# SPI2Parallel_v1p1.net
KiCad netlist of a schematic drawn in EAGLE
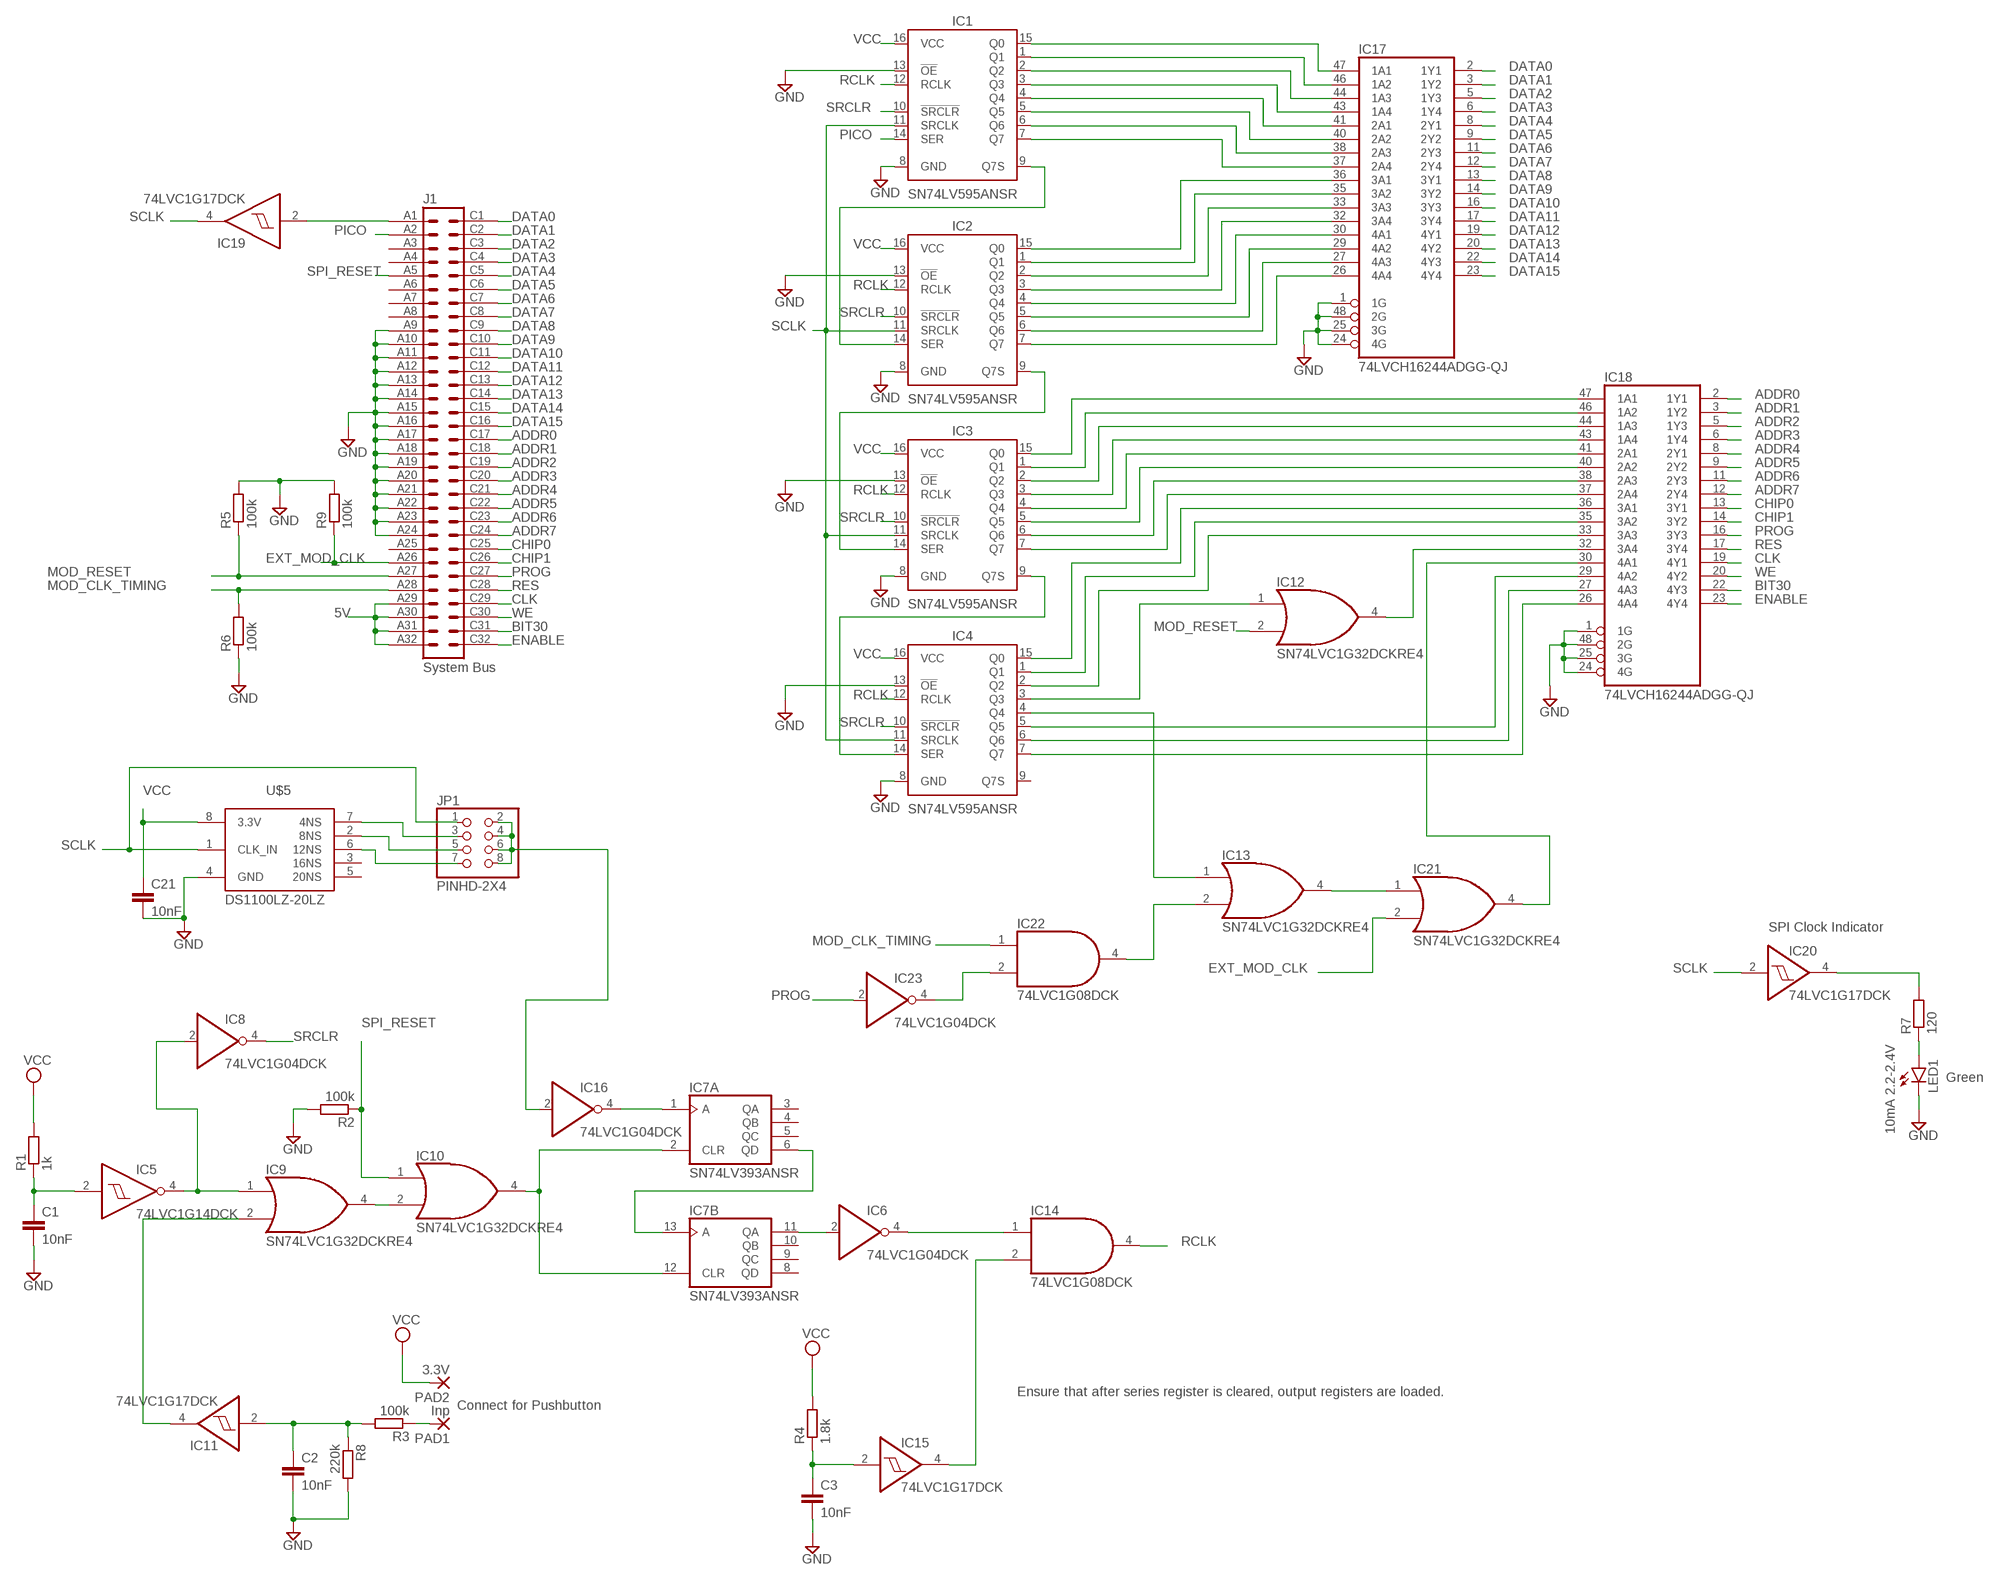
[diagram p0: schematic, sheet 1]
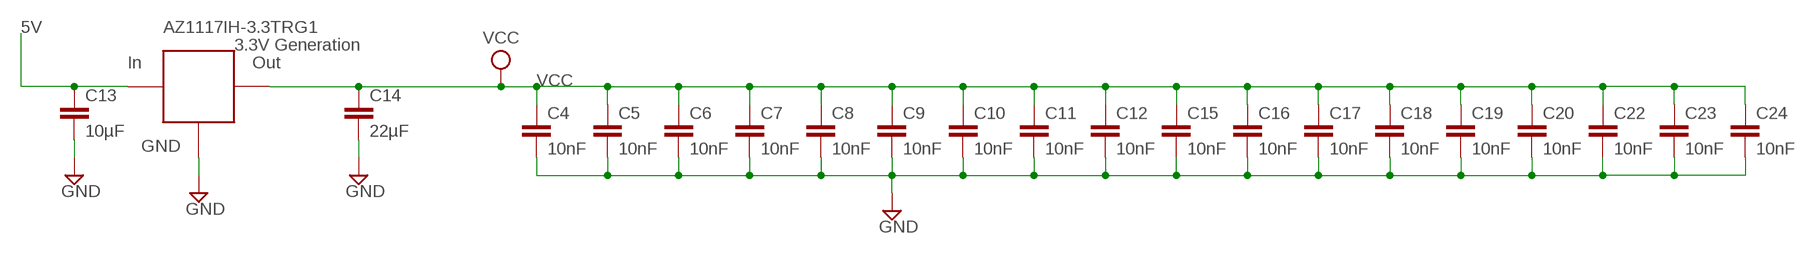
[diagram p1: schematic, sheet 2]

(export (version "E")
  (design (tool "Eeschema 10.0.6"))
  (components
    (comp (ref "C1")
      (value "10nF")
      (footprint "eagle-import:C0603")
      (libsource (lib "eagle-import") (part "C-EUC0603"))
    )
    (comp (ref "C2")
      (value "10nF")
      (footprint "eagle-import:C0603")
      (libsource (lib "eagle-import") (part "C-EUC0603"))
    )
    (comp (ref "C3")
      (value "10nF")
      (footprint "eagle-import:C0603")
      (libsource (lib "eagle-import") (part "C-EUC0603"))
    )
    (comp (ref "C21")
      (value "10nF")
      (footprint "eagle-import:C0603")
      (libsource (lib "eagle-import") (part "C-EUC0603"))
    )
    (comp (ref "IC1")
      (value "SN74LV595ANSR")
      (footprint "eagle-import:SOIC127P600X175-16N")
      (fields (field (name "MANUFACTURER") "Generic"))
      (libsource (lib "eagle-import") (part "74HC595_SOIC"))
    )
    (comp (ref "IC2")
      (value "SN74LV595ANSR")
      (footprint "eagle-import:SOIC127P600X175-16N")
      (fields (field (name "MANUFACTURER") "Generic"))
      (libsource (lib "eagle-import") (part "74HC595_SOIC"))
    )
    (comp (ref "IC3")
      (value "SN74LV595ANSR")
      (footprint "eagle-import:SOIC127P600X175-16N")
      (fields (field (name "MANUFACTURER") "Generic"))
      (libsource (lib "eagle-import") (part "74HC595_SOIC"))
    )
    (comp (ref "IC4")
      (value "SN74LV595ANSR")
      (footprint "eagle-import:SOIC127P600X175-16N")
      (fields (field (name "MANUFACTURER") "Generic"))
      (libsource (lib "eagle-import") (part "74HC595_SOIC"))
    )
    (comp (ref "IC5")
      (value "74LVC1G14DCK")
      (footprint "eagle-import:SC70-5")
      (libsource (lib "eagle-import") (part "741G14DCKLVC"))
    )
    (comp (ref "IC6")
      (value "74LVC1G04DCK")
      (footprint "eagle-import:SC70-5")
      (libsource (lib "eagle-import") (part "741G04DCKLVC"))
    )
    (comp (ref "IC7")
      (value "SN74LV393ANSR")
      (footprint "eagle-import:SO14")
      (libsource (lib "eagle-import") (part "74393DAC"))
    )
    (comp (ref "IC8")
      (value "74LVC1G04DCK")
      (footprint "eagle-import:SC70-5")
      (libsource (lib "eagle-import") (part "741G04DCKLVC"))
    )
    (comp (ref "IC9")
      (value "SN74LVC1G32DCKRE4")
      (footprint "eagle-import:SC70-5")
      (libsource (lib "eagle-import") (part "741G32DCKAHCT"))
    )
    (comp (ref "IC10")
      (value "SN74LVC1G32DCKRE4")
      (footprint "eagle-import:SC70-5")
      (libsource (lib "eagle-import") (part "741G32DCKAHCT"))
    )
    (comp (ref "IC11")
      (value "74LVC1G17DCK")
      (footprint "eagle-import:SC70-5")
      (libsource (lib "eagle-import") (part "741G17DCKLVC"))
    )
    (comp (ref "IC12")
      (value "SN74LVC1G32DCKRE4")
      (footprint "eagle-import:SC70-5")
      (libsource (lib "eagle-import") (part "741G32DCKAUC"))
    )
    (comp (ref "IC13")
      (value "SN74LVC1G32DCKRE4")
      (footprint "eagle-import:SC70-5")
      (libsource (lib "eagle-import") (part "741G32DCKAUC"))
    )
    (comp (ref "IC14")
      (value "74LVC1G08DCK")
      (footprint "eagle-import:SC70-5")
      (libsource (lib "eagle-import") (part "741G08DCKLVC"))
    )
    (comp (ref "IC15")
      (value "74LVC1G17DCK")
      (footprint "eagle-import:SC70-5")
      (libsource (lib "eagle-import") (part "741G17DCKLVC"))
    )
    (comp (ref "IC16")
      (value "74LVC1G04DCK")
      (footprint "eagle-import:SC70-5")
      (libsource (lib "eagle-import") (part "741G04DCKLVC"))
    )
    (comp (ref "IC17")
      (value "74LVCH16244ADGG-QJ")
      (footprint "eagle-import:SSOP48DL")
      (libsource (lib "eagle-import") (part "74AC16244"))
    )
    (comp (ref "IC18")
      (value "74LVCH16244ADGG-QJ")
      (footprint "eagle-import:SSOP48DL")
      (libsource (lib "eagle-import") (part "74AC16244"))
    )
    (comp (ref "IC19")
      (value "74LVC1G17DCK")
      (footprint "eagle-import:SC70-5")
      (libsource (lib "eagle-import") (part "74xx-little-us_87_741G17DCKLVC"))
    )
    (comp (ref "IC20")
      (value "74LVC1G17DCK")
      (footprint "eagle-import:SC70-5")
      (libsource (lib "eagle-import") (part "741G17DCKLVC"))
    )
    (comp (ref "IC21")
      (value "SN74LVC1G32DCKRE4")
      (footprint "eagle-import:SC70-5")
      (libsource (lib "eagle-import") (part "741G32DCKAUC"))
    )
    (comp (ref "IC22")
      (value "74LVC1G08DCK")
      (footprint "eagle-import:SC70-5")
      (libsource (lib "eagle-import") (part "741G08DCKLVC"))
    )
    (comp (ref "IC23")
      (value "74LVC1G04DCK")
      (footprint "eagle-import:SC70-5")
      (libsource (lib "eagle-import") (part "741G04DCKLVC"))
    )
    (comp (ref "J1")
      (value "System Bus")
      (footprint "eagle-import:VG64P")
      (libsource (lib "eagle-import") (part "VG64P"))
    )
    (comp (ref "JP1")
      (value "PINHD-2X4")
      (footprint "eagle-import:2X04")
      (libsource (lib "eagle-import") (part "PINHD-2X4"))
    )
    (comp (ref "LED1")
      (value "10mA 2.2-2.4V")
      (footprint "eagle-import:LED3MM")
      (libsource (lib "eagle-import") (part "LED3MM"))
    )
    (comp (ref "PAD1")
      (value "Inp")
      (footprint "eagle-import:SMD2,54-5,08")
      (libsource (lib "eagle-import") (part "SMD5"))
    )
    (comp (ref "PAD2")
      (value "3.3V")
      (footprint "eagle-import:SMD2,54-5,08")
      (libsource (lib "eagle-import") (part "SMD5"))
    )
    (comp (ref "R1")
      (value "1k")
      (footprint "eagle-import:R0603")
      (libsource (lib "eagle-import") (part "R-EU_R0603"))
    )
    (comp (ref "R2")
      (value "100k")
      (footprint "eagle-import:R0603")
      (libsource (lib "eagle-import") (part "R-EU_R0603"))
    )
    (comp (ref "R3")
      (value "100k")
      (footprint "eagle-import:R0603")
      (libsource (lib "eagle-import") (part "R-EU_R0603"))
    )
    (comp (ref "R4")
      (value "1.8k")
      (footprint "eagle-import:R0603")
      (libsource (lib "eagle-import") (part "R-EU_R0603"))
    )
    (comp (ref "R5")
      (value "100k")
      (footprint "eagle-import:R0603")
      (libsource (lib "eagle-import") (part "R-EU_R0603"))
    )
    (comp (ref "R6")
      (value "100k")
      (footprint "eagle-import:R0603")
      (libsource (lib "eagle-import") (part "R-EU_R0603"))
    )
    (comp (ref "R7")
      (value "120")
      (footprint "eagle-import:R0603")
      (libsource (lib "eagle-import") (part "R-EU_R0603"))
    )
    (comp (ref "R8")
      (value "220k")
      (footprint "eagle-import:R0603")
      (libsource (lib "eagle-import") (part "R-EU_R0603"))
    )
    (comp (ref "R9")
      (value "100k")
      (footprint "eagle-import:R0603")
      (libsource (lib "eagle-import") (part "R-EU_R0603"))
    )
    (comp (ref "U$5")
      (value "DS1100LZ-20LZ")
      (footprint "eagle-import:SO-08")
      (libsource (lib "eagle-import") (part "DS1100LZ-20LZ"))
    )
    (comp (ref "C4")
      (value "10nF")
      (footprint "eagle-import:C0603")
      (libsource (lib "eagle-import") (part "C-EUC0603"))
    )
    (comp (ref "C5")
      (value "10nF")
      (footprint "eagle-import:C0603")
      (libsource (lib "eagle-import") (part "C-EUC0603"))
    )
    (comp (ref "C6")
      (value "10nF")
      (footprint "eagle-import:C0603")
      (libsource (lib "eagle-import") (part "C-EUC0603"))
    )
    (comp (ref "C7")
      (value "10nF")
      (footprint "eagle-import:C0603")
      (libsource (lib "eagle-import") (part "C-EUC0603"))
    )
    (comp (ref "C8")
      (value "10nF")
      (footprint "eagle-import:C0603")
      (libsource (lib "eagle-import") (part "C-EUC0603"))
    )
    (comp (ref "C9")
      (value "10nF")
      (footprint "eagle-import:C0603")
      (libsource (lib "eagle-import") (part "C-EUC0603"))
    )
    (comp (ref "C10")
      (value "10nF")
      (footprint "eagle-import:C0603")
      (libsource (lib "eagle-import") (part "C-EUC0603"))
    )
    (comp (ref "C11")
      (value "10nF")
      (footprint "eagle-import:C0603")
      (libsource (lib "eagle-import") (part "C-EUC0603"))
    )
    (comp (ref "C12")
      (value "10nF")
      (footprint "eagle-import:C0603")
      (libsource (lib "eagle-import") (part "C-EUC0603"))
    )
    (comp (ref "C13")
      (value "10µF")
      (footprint "eagle-import:C1206")
      (libsource (lib "eagle-import") (part "C-EUC1206"))
    )
    (comp (ref "C14")
      (value "22µF")
      (footprint "eagle-import:C1206")
      (libsource (lib "eagle-import") (part "C-EUC1206"))
    )
    (comp (ref "C15")
      (value "10nF")
      (footprint "eagle-import:C0603")
      (libsource (lib "eagle-import") (part "C-EUC0603"))
    )
    (comp (ref "C16")
      (value "10nF")
      (footprint "eagle-import:C0603")
      (libsource (lib "eagle-import") (part "C-EUC0603"))
    )
    (comp (ref "C17")
      (value "10nF")
      (footprint "eagle-import:C0603")
      (libsource (lib "eagle-import") (part "C-EUC0603"))
    )
    (comp (ref "C18")
      (value "10nF")
      (footprint "eagle-import:C0603")
      (libsource (lib "eagle-import") (part "C-EUC0603"))
    )
    (comp (ref "C19")
      (value "10nF")
      (footprint "eagle-import:C0603")
      (libsource (lib "eagle-import") (part "C-EUC0603"))
    )
    (comp (ref "C20")
      (value "10nF")
      (footprint "eagle-import:C0603")
      (libsource (lib "eagle-import") (part "C-EUC0603"))
    )
    (comp (ref "C22")
      (value "10nF")
      (footprint "eagle-import:C0603")
      (libsource (lib "eagle-import") (part "C-EUC0603"))
    )
    (comp (ref "C23")
      (value "10nF")
      (footprint "eagle-import:C0603")
      (libsource (lib "eagle-import") (part "C-EUC0603"))
    )
    (comp (ref "C24")
      (value "10nF")
      (footprint "eagle-import:C0603")
      (libsource (lib "eagle-import") (part "C-EUC0603"))
    )
    (comp (ref "U$9")
      (value "AZ1117IH-3.3TRG1")
      (footprint "eagle-import:SOT223")
      (libsource (lib "eagle-import") (part "LT1117"))
    )
  )
  (nets
    (net (code "1") (name "5V") (class "Default")
      (node (ref "C13") (pin "1") (pinfunction "1_1") (pintype "passive"))
      (node (ref "J1") (pin "A29") (pinfunction "A29_A29") (pintype "passive"))
      (node (ref "J1") (pin "A30") (pinfunction "A30_A30") (pintype "passive"))
      (node (ref "J1") (pin "A31") (pinfunction "A31_A31") (pintype "passive"))
      (node (ref "J1") (pin "A32") (pinfunction "A32_A32") (pintype "passive"))
      (node (ref "U$9") (pin "3") (pinfunction "IN_3") (pintype "bidirectional"))
    )
    (net (code "2") (name "ADDR0") (class "Default")
      (node (ref "IC18") (pin "2") (pinfunction "1Y1_2") (pintype "tri_state"))
      (node (ref "J1") (pin "C17") (pinfunction "C17_C17") (pintype "passive"))
    )
    (net (code "3") (name "ADDR1") (class "Default")
      (node (ref "IC18") (pin "3") (pinfunction "1Y2_3") (pintype "tri_state"))
      (node (ref "J1") (pin "C18") (pinfunction "C18_C18") (pintype "passive"))
    )
    (net (code "4") (name "ADDR2") (class "Default")
      (node (ref "IC18") (pin "5") (pinfunction "1Y3_5") (pintype "tri_state"))
      (node (ref "J1") (pin "C19") (pinfunction "C19_C19") (pintype "passive"))
    )
    (net (code "5") (name "ADDR3") (class "Default")
      (node (ref "IC18") (pin "6") (pinfunction "1Y4_6") (pintype "tri_state"))
      (node (ref "J1") (pin "C20") (pinfunction "C20_C20") (pintype "passive"))
    )
    (net (code "6") (name "ADDR4") (class "Default")
      (node (ref "IC18") (pin "8") (pinfunction "2Y1_8") (pintype "tri_state"))
      (node (ref "J1") (pin "C21") (pinfunction "C21_C21") (pintype "passive"))
    )
    (net (code "7") (name "ADDR5") (class "Default")
      (node (ref "IC18") (pin "9") (pinfunction "2Y2_9") (pintype "tri_state"))
      (node (ref "J1") (pin "C22") (pinfunction "C22_C22") (pintype "passive"))
    )
    (net (code "8") (name "ADDR6") (class "Default")
      (node (ref "IC18") (pin "11") (pinfunction "2Y3_11") (pintype "tri_state"))
      (node (ref "J1") (pin "C23") (pinfunction "C23_C23") (pintype "passive"))
    )
    (net (code "9") (name "ADDR7") (class "Default")
      (node (ref "IC18") (pin "12") (pinfunction "2Y4_12") (pintype "tri_state"))
      (node (ref "J1") (pin "C24") (pinfunction "C24_C24") (pintype "passive"))
    )
    (net (code "10") (name "BIT30") (class "Default")
      (node (ref "IC18") (pin "22") (pinfunction "4Y3_22") (pintype "tri_state"))
      (node (ref "J1") (pin "C31") (pinfunction "C31_C31") (pintype "passive"))
    )
    (net (code "11") (name "CHIP0") (class "Default")
      (node (ref "IC18") (pin "13") (pinfunction "3Y1_13") (pintype "tri_state"))
      (node (ref "J1") (pin "C25") (pinfunction "C25_C25") (pintype "passive"))
    )
    (net (code "12") (name "CHIP1") (class "Default")
      (node (ref "IC18") (pin "14") (pinfunction "3Y2_14") (pintype "tri_state"))
      (node (ref "J1") (pin "C26") (pinfunction "C26_C26") (pintype "passive"))
    )
    (net (code "13") (name "CLK") (class "Default")
      (node (ref "IC18") (pin "19") (pinfunction "4Y1_19") (pintype "tri_state"))
      (node (ref "J1") (pin "C29") (pinfunction "C29_C29") (pintype "passive"))
    )
    (net (code "14") (name "DATA0") (class "Default")
      (node (ref "IC17") (pin "2") (pinfunction "1Y1_2") (pintype "tri_state"))
      (node (ref "J1") (pin "C1") (pinfunction "C1_C1") (pintype "passive"))
    )
    (net (code "15") (name "DATA1") (class "Default")
      (node (ref "IC17") (pin "3") (pinfunction "1Y2_3") (pintype "tri_state"))
      (node (ref "J1") (pin "C2") (pinfunction "C2_C2") (pintype "passive"))
    )
    (net (code "16") (name "DATA2") (class "Default")
      (node (ref "IC17") (pin "5") (pinfunction "1Y3_5") (pintype "tri_state"))
      (node (ref "J1") (pin "C3") (pinfunction "C3_C3") (pintype "passive"))
    )
    (net (code "17") (name "DATA3") (class "Default")
      (node (ref "IC17") (pin "6") (pinfunction "1Y4_6") (pintype "tri_state"))
      (node (ref "J1") (pin "C4") (pinfunction "C4_C4") (pintype "passive"))
    )
    (net (code "18") (name "DATA4") (class "Default")
      (node (ref "IC17") (pin "8") (pinfunction "2Y1_8") (pintype "tri_state"))
      (node (ref "J1") (pin "C5") (pinfunction "C5_C5") (pintype "passive"))
    )
    (net (code "19") (name "DATA5") (class "Default")
      (node (ref "IC17") (pin "9") (pinfunction "2Y2_9") (pintype "tri_state"))
      (node (ref "J1") (pin "C6") (pinfunction "C6_C6") (pintype "passive"))
    )
    (net (code "20") (name "DATA6") (class "Default")
      (node (ref "IC17") (pin "11") (pinfunction "2Y3_11") (pintype "tri_state"))
      (node (ref "J1") (pin "C7") (pinfunction "C7_C7") (pintype "passive"))
    )
    (net (code "21") (name "DATA7") (class "Default")
      (node (ref "IC17") (pin "12") (pinfunction "2Y4_12") (pintype "tri_state"))
      (node (ref "J1") (pin "C8") (pinfunction "C8_C8") (pintype "passive"))
    )
    (net (code "22") (name "DATA8") (class "Default")
      (node (ref "IC17") (pin "13") (pinfunction "3Y1_13") (pintype "tri_state"))
      (node (ref "J1") (pin "C9") (pinfunction "C9_C9") (pintype "passive"))
    )
    (net (code "23") (name "DATA9") (class "Default")
      (node (ref "IC17") (pin "14") (pinfunction "3Y2_14") (pintype "tri_state"))
      (node (ref "J1") (pin "C10") (pinfunction "C10_C10") (pintype "passive"))
    )
    (net (code "24") (name "DATA10") (class "Default")
      (node (ref "IC17") (pin "16") (pinfunction "3Y3_16") (pintype "tri_state"))
      (node (ref "J1") (pin "C11") (pinfunction "C11_C11") (pintype "passive"))
    )
    (net (code "25") (name "DATA11") (class "Default")
      (node (ref "IC17") (pin "17") (pinfunction "3Y4_17") (pintype "tri_state"))
      (node (ref "J1") (pin "C12") (pinfunction "C12_C12") (pintype "passive"))
    )
    (net (code "26") (name "DATA12") (class "Default")
      (node (ref "IC17") (pin "19") (pinfunction "4Y1_19") (pintype "tri_state"))
      (node (ref "J1") (pin "C13") (pinfunction "C13_C13") (pintype "passive"))
    )
    (net (code "27") (name "DATA13") (class "Default")
      (node (ref "IC17") (pin "20") (pinfunction "4Y2_20") (pintype "tri_state"))
      (node (ref "J1") (pin "C14") (pinfunction "C14_C14") (pintype "passive"))
    )
    (net (code "28") (name "DATA14") (class "Default")
      (node (ref "IC17") (pin "22") (pinfunction "4Y3_22") (pintype "tri_state"))
      (node (ref "J1") (pin "C15") (pinfunction "C15_C15") (pintype "passive"))
    )
    (net (code "29") (name "DATA15") (class "Default")
      (node (ref "IC17") (pin "23") (pinfunction "4Y4_23") (pintype "tri_state"))
      (node (ref "J1") (pin "C16") (pinfunction "C16_C16") (pintype "passive"))
    )
    (net (code "30") (name "ENABLE") (class "Default")
      (node (ref "IC18") (pin "23") (pinfunction "4Y4_23") (pintype "tri_state"))
      (node (ref "J1") (pin "C32") (pinfunction "C32_C32") (pintype "passive"))
    )
    (net (code "31") (name "EXT_MOD_CLK") (class "Default")
      (node (ref "IC21") (pin "2") (pinfunction "I1_2") (pintype "input"))
      (node (ref "J1") (pin "A26") (pinfunction "A26_A26") (pintype "passive"))
      (node (ref "R9") (pin "1") (pinfunction "1_1") (pintype "passive"))
    )
    (net (code "32") (name "GND") (class "Default")
      (node (ref "C1") (pin "2") (pinfunction "2_2") (pintype "passive"))
      (node (ref "C10") (pin "2") (pinfunction "2_2") (pintype "passive"))
      (node (ref "C11") (pin "2") (pinfunction "2_2") (pintype "passive"))
      (node (ref "C12") (pin "2") (pinfunction "2_2") (pintype "passive"))
      (node (ref "C13") (pin "2") (pinfunction "2_2") (pintype "passive"))
      (node (ref "C14") (pin "2") (pinfunction "2_2") (pintype "passive"))
      (node (ref "C15") (pin "2") (pinfunction "2_2") (pintype "passive"))
      (node (ref "C16") (pin "2") (pinfunction "2_2") (pintype "passive"))
      (node (ref "C17") (pin "2") (pinfunction "2_2") (pintype "passive"))
      (node (ref "C18") (pin "2") (pinfunction "2_2") (pintype "passive"))
      (node (ref "C19") (pin "2") (pinfunction "2_2") (pintype "passive"))
      (node (ref "C2") (pin "2") (pinfunction "2_2") (pintype "passive"))
      (node (ref "C20") (pin "2") (pinfunction "2_2") (pintype "passive"))
      (node (ref "C21") (pin "2") (pinfunction "2_2") (pintype "passive"))
      (node (ref "C22") (pin "2") (pinfunction "2_2") (pintype "passive"))
      (node (ref "C23") (pin "2") (pinfunction "2_2") (pintype "passive"))
      (node (ref "C24") (pin "2") (pinfunction "2_2") (pintype "passive"))
      (node (ref "C3") (pin "2") (pinfunction "2_2") (pintype "passive"))
      (node (ref "C4") (pin "2") (pinfunction "2_2") (pintype "passive"))
      (node (ref "C5") (pin "2") (pinfunction "2_2") (pintype "passive"))
      (node (ref "C6") (pin "2") (pinfunction "2_2") (pintype "passive"))
      (node (ref "C7") (pin "2") (pinfunction "2_2") (pintype "passive"))
      (node (ref "C8") (pin "2") (pinfunction "2_2") (pintype "passive"))
      (node (ref "C9") (pin "2") (pinfunction "2_2") (pintype "passive"))
      (node (ref "IC1") (pin "13") (pinfunction "~{OE}_13") (pintype "output"))
      (node (ref "IC1") (pin "8") (pinfunction "GND_8") (pintype "bidirectional"))
      (node (ref "IC17") (pin "1") (pinfunction "1G_1") (pintype "input"))
      (node (ref "IC17") (pin "24") (pinfunction "4G_24") (pintype "input"))
      (node (ref "IC17") (pin "25") (pinfunction "3G_25") (pintype "input"))
      (node (ref "IC17") (pin "48") (pinfunction "2G_48") (pintype "input"))
      (node (ref "IC18") (pin "1") (pinfunction "1G_1") (pintype "input"))
      (node (ref "IC18") (pin "24") (pinfunction "4G_24") (pintype "input"))
      (node (ref "IC18") (pin "25") (pinfunction "3G_25") (pintype "input"))
      (node (ref "IC18") (pin "48") (pinfunction "2G_48") (pintype "input"))
      (node (ref "IC2") (pin "13") (pinfunction "~{OE}_13") (pintype "output"))
      (node (ref "IC2") (pin "8") (pinfunction "GND_8") (pintype "bidirectional"))
      (node (ref "IC3") (pin "13") (pinfunction "~{OE}_13") (pintype "output"))
      (node (ref "IC3") (pin "8") (pinfunction "GND_8") (pintype "bidirectional"))
      (node (ref "IC4") (pin "13") (pinfunction "~{OE}_13") (pintype "output"))
      (node (ref "IC4") (pin "8") (pinfunction "GND_8") (pintype "bidirectional"))
      (node (ref "J1") (pin "A10") (pinfunction "A10_A10") (pintype "passive"))
      (node (ref "J1") (pin "A11") (pinfunction "A11_A11") (pintype "passive"))
      (node (ref "J1") (pin "A12") (pinfunction "A12_A12") (pintype "passive"))
      (node (ref "J1") (pin "A13") (pinfunction "A13_A13") (pintype "passive"))
      (node (ref "J1") (pin "A14") (pinfunction "A14_A14") (pintype "passive"))
      (node (ref "J1") (pin "A15") (pinfunction "A15_A15") (pintype "passive"))
      (node (ref "J1") (pin "A16") (pinfunction "A16_A16") (pintype "passive"))
      (node (ref "J1") (pin "A17") (pinfunction "A17_A17") (pintype "passive"))
      (node (ref "J1") (pin "A18") (pinfunction "A18_A18") (pintype "passive"))
      (node (ref "J1") (pin "A19") (pinfunction "A19_A19") (pintype "passive"))
      (node (ref "J1") (pin "A20") (pinfunction "A20_A20") (pintype "passive"))
      (node (ref "J1") (pin "A21") (pinfunction "A21_A21") (pintype "passive"))
      (node (ref "J1") (pin "A22") (pinfunction "A22_A22") (pintype "passive"))
      (node (ref "J1") (pin "A23") (pinfunction "A23_A23") (pintype "passive"))
      (node (ref "J1") (pin "A24") (pinfunction "A24_A24") (pintype "passive"))
      (node (ref "J1") (pin "A9") (pinfunction "A9_A9") (pintype "passive"))
      (node (ref "LED1") (pin "K") (pinfunction "C_K") (pintype "passive"))
      (node (ref "R2") (pin "2") (pinfunction "2_2") (pintype "passive"))
      (node (ref "R5") (pin "2") (pinfunction "2_2") (pintype "passive"))
      (node (ref "R6") (pin "1") (pinfunction "1_1") (pintype "passive"))
      (node (ref "R8") (pin "2") (pinfunction "2_2") (pintype "passive"))
      (node (ref "R9") (pin "2") (pinfunction "2_2") (pintype "passive"))
      (node (ref "U$5") (pin "4") (pinfunction "GND_4") (pintype "bidirectional"))
      (node (ref "U$9") (pin "1") (pinfunction "GND_1") (pintype "bidirectional"))
    )
    (net (code "33") (name "MOD_CLK_TIMING") (class "Default")
      (node (ref "IC22") (pin "1") (pinfunction "I0_1") (pintype "input"))
      (node (ref "J1") (pin "A28") (pinfunction "A28_A28") (pintype "passive"))
      (node (ref "R6") (pin "2") (pinfunction "2_2") (pintype "passive"))
    )
    (net (code "34") (name "MOD_RESET") (class "Default")
      (node (ref "IC12") (pin "2") (pinfunction "I1_2") (pintype "input"))
      (node (ref "J1") (pin "A27") (pinfunction "A27_A27") (pintype "passive"))
      (node (ref "R5") (pin "1") (pinfunction "1_1") (pintype "passive"))
    )
    (net (code "35") (name "Net-(IC1-Q0)") (class "Default")
      (node (ref "IC1") (pin "15") (pinfunction "Q0_15") (pintype "output"))
      (node (ref "IC17") (pin "47") (pinfunction "1A1_47") (pintype "input"))
    )
    (net (code "36") (name "Net-(IC1-Q1)") (class "Default")
      (node (ref "IC1") (pin "1") (pinfunction "Q1_1") (pintype "output"))
      (node (ref "IC17") (pin "46") (pinfunction "1A2_46") (pintype "input"))
    )
    (net (code "37") (name "Net-(IC1-Q2)") (class "Default")
      (node (ref "IC1") (pin "2") (pinfunction "Q2_2") (pintype "output"))
      (node (ref "IC17") (pin "44") (pinfunction "1A3_44") (pintype "input"))
    )
    (net (code "38") (name "Net-(IC1-Q3)") (class "Default")
      (node (ref "IC1") (pin "3") (pinfunction "Q3_3") (pintype "output"))
      (node (ref "IC17") (pin "43") (pinfunction "1A4_43") (pintype "input"))
    )
    (net (code "39") (name "Net-(IC1-Q4)") (class "Default")
      (node (ref "IC1") (pin "4") (pinfunction "Q4_4") (pintype "output"))
      (node (ref "IC17") (pin "41") (pinfunction "2A1_41") (pintype "input"))
    )
    (net (code "40") (name "Net-(IC1-Q5)") (class "Default")
      (node (ref "IC1") (pin "5") (pinfunction "Q5_5") (pintype "output"))
      (node (ref "IC17") (pin "40") (pinfunction "2A2_40") (pintype "input"))
    )
    (net (code "41") (name "Net-(IC1-Q6)") (class "Default")
      (node (ref "IC1") (pin "6") (pinfunction "Q6_6") (pintype "output"))
      (node (ref "IC17") (pin "38") (pinfunction "2A3_38") (pintype "input"))
    )
    (net (code "42") (name "Net-(IC1-Q7)") (class "Default")
      (node (ref "IC1") (pin "7") (pinfunction "Q7_7") (pintype "output"))
      (node (ref "IC17") (pin "37") (pinfunction "2A4_37") (pintype "input"))
    )
    (net (code "43") (name "Net-(IC1-Q7S)") (class "Default")
      (node (ref "IC1") (pin "9") (pinfunction "Q7S_9") (pintype "output"))
      (node (ref "IC2") (pin "14") (pinfunction "SER_14") (pintype "input"))
    )
    (net (code "44") (name "Net-(IC2-Q7S)") (class "Default")
      (node (ref "IC2") (pin "9") (pinfunction "Q7S_9") (pintype "output"))
      (node (ref "IC3") (pin "14") (pinfunction "SER_14") (pintype "input"))
    )
    (net (code "45") (name "Net-(IC3-Q7S)") (class "Default")
      (node (ref "IC3") (pin "9") (pinfunction "Q7S_9") (pintype "output"))
      (node (ref "IC4") (pin "14") (pinfunction "SER_14") (pintype "input"))
    )
    (net (code "46") (name "Net-(IC5A-I)") (class "Default")
      (node (ref "C1") (pin "1") (pinfunction "1_1") (pintype "passive"))
      (node (ref "IC5") (pin "2") (pinfunction "I_2") (pintype "input"))
      (node (ref "R1") (pin "1") (pinfunction "1_1") (pintype "passive"))
    )
    (net (code "47") (name "Net-(IC5A-O)") (class "Default")
      (node (ref "IC5") (pin "4") (pinfunction "O_4") (pintype "output"))
      (node (ref "IC8") (pin "2") (pinfunction "I_2") (pintype "input"))
      (node (ref "IC9") (pin "1") (pinfunction "I0_1") (pintype "input"))
    )
    (net (code "48") (name "Net-(IC6A-I)") (class "Default")
      (node (ref "IC6") (pin "2") (pinfunction "I_2") (pintype "input"))
      (node (ref "IC7") (pin "11") (pinfunction "QA_11") (pintype "output"))
    )
    (net (code "49") (name "Net-(IC7A-QD)") (class "Default")
      (node (ref "IC7") (pin "13") (pinfunction "A_13") (pintype "input"))
      (node (ref "IC7") (pin "6") (pinfunction "QD_6") (pintype "output"))
    )
    (net (code "50") (name "Net-(IC10A-I1)") (class "Default")
      (node (ref "IC10") (pin "2") (pinfunction "I1_2") (pintype "input"))
      (node (ref "IC9") (pin "4") (pinfunction "O_4") (pintype "output"))
    )
    (net (code "51") (name "Net-(IC10A-O)") (class "Default")
      (node (ref "IC10") (pin "4") (pinfunction "O_4") (pintype "output"))
      (node (ref "IC7") (pin "12") (pinfunction "CLR_12") (pintype "input"))
      (node (ref "IC7") (pin "2") (pinfunction "CLR_2") (pintype "input"))
    )
    (net (code "52") (name "Net-(IC11A-I)") (class "Default")
      (node (ref "C2") (pin "1") (pinfunction "1_1") (pintype "passive"))
      (node (ref "IC11") (pin "2") (pinfunction "I_2") (pintype "input"))
      (node (ref "R3") (pin "2") (pinfunction "2_2") (pintype "passive"))
      (node (ref "R8") (pin "1") (pinfunction "1_1") (pintype "passive"))
    )
    (net (code "53") (name "Net-(IC11A-O)") (class "Default")
      (node (ref "IC11") (pin "4") (pinfunction "O_4") (pintype "output"))
      (node (ref "IC9") (pin "2") (pinfunction "I1_2") (pintype "input"))
    )
    (net (code "54") (name "Net-(IC12A-I0)") (class "Default")
      (node (ref "IC12") (pin "1") (pinfunction "I0_1") (pintype "input"))
      (node (ref "IC4") (pin "3") (pinfunction "Q3_3") (pintype "output"))
    )
    (net (code "55") (name "Net-(IC12A-O)") (class "Default")
      (node (ref "IC12") (pin "4") (pinfunction "O_4") (pintype "output"))
      (node (ref "IC18") (pin "32") (pinfunction "3A4_32") (pintype "input"))
    )
    (net (code "56") (name "Net-(IC13A-I0)") (class "Default")
      (node (ref "IC13") (pin "1") (pinfunction "I0_1") (pintype "input"))
      (node (ref "IC4") (pin "4") (pinfunction "Q4_4") (pintype "output"))
    )
    (net (code "57") (name "Net-(IC13A-I1)") (class "Default")
      (node (ref "IC13") (pin "2") (pinfunction "I1_2") (pintype "input"))
      (node (ref "IC22") (pin "4") (pinfunction "O_4") (pintype "output"))
    )
    (net (code "58") (name "Net-(IC13A-O)") (class "Default")
      (node (ref "IC13") (pin "4") (pinfunction "O_4") (pintype "output"))
      (node (ref "IC21") (pin "1") (pinfunction "I0_1") (pintype "input"))
    )
    (net (code "59") (name "Net-(IC14A-I0)") (class "Default")
      (node (ref "IC14") (pin "1") (pinfunction "I0_1") (pintype "input"))
      (node (ref "IC6") (pin "4") (pinfunction "O_4") (pintype "output"))
    )
    (net (code "60") (name "Net-(IC14A-I1)") (class "Default")
      (node (ref "IC14") (pin "2") (pinfunction "I1_2") (pintype "input"))
      (node (ref "IC15") (pin "4") (pinfunction "O_4") (pintype "output"))
    )
    (net (code "61") (name "Net-(IC15A-I)") (class "Default")
      (node (ref "C3") (pin "1") (pinfunction "1_1") (pintype "passive"))
      (node (ref "IC15") (pin "2") (pinfunction "I_2") (pintype "input"))
      (node (ref "R4") (pin "1") (pinfunction "1_1") (pintype "passive"))
    )
    (net (code "62") (name "Net-(IC16A-I)") (class "Default")
      (node (ref "IC16") (pin "2") (pinfunction "I_2") (pintype "input"))
      (node (ref "JP1") (pin "2") (pinfunction "2_2") (pintype "passive"))
      (node (ref "JP1") (pin "4") (pinfunction "4_4") (pintype "passive"))
      (node (ref "JP1") (pin "6") (pinfunction "6_6") (pintype "passive"))
      (node (ref "JP1") (pin "8") (pinfunction "8_8") (pintype "passive"))
    )
    (net (code "63") (name "Net-(IC16A-O)") (class "Default")
      (node (ref "IC16") (pin "4") (pinfunction "O_4") (pintype "output"))
      (node (ref "IC7") (pin "1") (pinfunction "A_1") (pintype "input"))
    )
    (net (code "64") (name "Net-(IC17A-3A1)") (class "Default")
      (node (ref "IC17") (pin "36") (pinfunction "3A1_36") (pintype "input"))
      (node (ref "IC2") (pin "15") (pinfunction "Q0_15") (pintype "output"))
    )
    (net (code "65") (name "Net-(IC17A-3A2)") (class "Default")
      (node (ref "IC17") (pin "35") (pinfunction "3A2_35") (pintype "input"))
      (node (ref "IC2") (pin "1") (pinfunction "Q1_1") (pintype "output"))
    )
    (net (code "66") (name "Net-(IC17A-3A3)") (class "Default")
      (node (ref "IC17") (pin "33") (pinfunction "3A3_33") (pintype "input"))
      (node (ref "IC2") (pin "2") (pinfunction "Q2_2") (pintype "output"))
    )
    (net (code "67") (name "Net-(IC17A-3A4)") (class "Default")
      (node (ref "IC17") (pin "32") (pinfunction "3A4_32") (pintype "input"))
      (node (ref "IC2") (pin "3") (pinfunction "Q3_3") (pintype "output"))
    )
    (net (code "68") (name "Net-(IC17A-4A1)") (class "Default")
      (node (ref "IC17") (pin "30") (pinfunction "4A1_30") (pintype "input"))
      (node (ref "IC2") (pin "4") (pinfunction "Q4_4") (pintype "output"))
    )
    (net (code "69") (name "Net-(IC17A-4A2)") (class "Default")
      (node (ref "IC17") (pin "29") (pinfunction "4A2_29") (pintype "input"))
      (node (ref "IC2") (pin "5") (pinfunction "Q5_5") (pintype "output"))
    )
    (net (code "70") (name "Net-(IC17A-4A3)") (class "Default")
      (node (ref "IC17") (pin "27") (pinfunction "4A3_27") (pintype "input"))
      (node (ref "IC2") (pin "6") (pinfunction "Q6_6") (pintype "output"))
    )
    (net (code "71") (name "Net-(IC17A-4A4)") (class "Default")
      (node (ref "IC17") (pin "26") (pinfunction "4A4_26") (pintype "input"))
      (node (ref "IC2") (pin "7") (pinfunction "Q7_7") (pintype "output"))
    )
    (net (code "72") (name "Net-(IC18A-1A1)") (class "Default")
      (node (ref "IC18") (pin "47") (pinfunction "1A1_47") (pintype "input"))
      (node (ref "IC3") (pin "15") (pinfunction "Q0_15") (pintype "output"))
    )
    (net (code "73") (name "Net-(IC18A-1A2)") (class "Default")
      (node (ref "IC18") (pin "46") (pinfunction "1A2_46") (pintype "input"))
      (node (ref "IC3") (pin "1") (pinfunction "Q1_1") (pintype "output"))
    )
    (net (code "74") (name "Net-(IC18A-1A3)") (class "Default")
      (node (ref "IC18") (pin "44") (pinfunction "1A3_44") (pintype "input"))
      (node (ref "IC3") (pin "2") (pinfunction "Q2_2") (pintype "output"))
    )
    (net (code "75") (name "Net-(IC18A-1A4)") (class "Default")
      (node (ref "IC18") (pin "43") (pinfunction "1A4_43") (pintype "input"))
      (node (ref "IC3") (pin "3") (pinfunction "Q3_3") (pintype "output"))
    )
    (net (code "76") (name "Net-(IC18A-2A1)") (class "Default")
      (node (ref "IC18") (pin "41") (pinfunction "2A1_41") (pintype "input"))
      (node (ref "IC3") (pin "4") (pinfunction "Q4_4") (pintype "output"))
    )
    (net (code "77") (name "Net-(IC18A-2A2)") (class "Default")
      (node (ref "IC18") (pin "40") (pinfunction "2A2_40") (pintype "input"))
      (node (ref "IC3") (pin "5") (pinfunction "Q5_5") (pintype "output"))
    )
    (net (code "78") (name "Net-(IC18A-2A3)") (class "Default")
      (node (ref "IC18") (pin "38") (pinfunction "2A3_38") (pintype "input"))
      (node (ref "IC3") (pin "6") (pinfunction "Q6_6") (pintype "output"))
    )
    (net (code "79") (name "Net-(IC18A-2A4)") (class "Default")
      (node (ref "IC18") (pin "37") (pinfunction "2A4_37") (pintype "input"))
      (node (ref "IC3") (pin "7") (pinfunction "Q7_7") (pintype "output"))
    )
    (net (code "80") (name "Net-(IC18A-3A1)") (class "Default")
      (node (ref "IC18") (pin "36") (pinfunction "3A1_36") (pintype "input"))
      (node (ref "IC4") (pin "15") (pinfunction "Q0_15") (pintype "output"))
    )
    (net (code "81") (name "Net-(IC18A-3A2)") (class "Default")
      (node (ref "IC18") (pin "35") (pinfunction "3A2_35") (pintype "input"))
      (node (ref "IC4") (pin "1") (pinfunction "Q1_1") (pintype "output"))
    )
    (net (code "82") (name "Net-(IC18A-3A3)") (class "Default")
      (node (ref "IC18") (pin "33") (pinfunction "3A3_33") (pintype "input"))
      (node (ref "IC4") (pin "2") (pinfunction "Q2_2") (pintype "output"))
    )
    (net (code "83") (name "Net-(IC18A-4A1)") (class "Default")
      (node (ref "IC18") (pin "30") (pinfunction "4A1_30") (pintype "input"))
      (node (ref "IC21") (pin "4") (pinfunction "O_4") (pintype "output"))
    )
    (net (code "84") (name "Net-(IC18A-4A2)") (class "Default")
      (node (ref "IC18") (pin "29") (pinfunction "4A2_29") (pintype "input"))
      (node (ref "IC4") (pin "5") (pinfunction "Q5_5") (pintype "output"))
    )
    (net (code "85") (name "Net-(IC18A-4A3)") (class "Default")
      (node (ref "IC18") (pin "27") (pinfunction "4A3_27") (pintype "input"))
      (node (ref "IC4") (pin "6") (pinfunction "Q6_6") (pintype "output"))
    )
    (net (code "86") (name "Net-(IC18A-4A4)") (class "Default")
      (node (ref "IC18") (pin "26") (pinfunction "4A4_26") (pintype "input"))
      (node (ref "IC4") (pin "7") (pinfunction "Q7_7") (pintype "output"))
    )
    (net (code "87") (name "Net-(IC19A-I)") (class "Default")
      (node (ref "IC19") (pin "2") (pinfunction "I_2") (pintype "input"))
      (node (ref "J1") (pin "A1") (pinfunction "A1_A1") (pintype "passive"))
    )
    (net (code "88") (name "Net-(IC20A-O)") (class "Default")
      (node (ref "IC20") (pin "4") (pinfunction "O_4") (pintype "output"))
      (node (ref "R7") (pin "2") (pinfunction "2_2") (pintype "passive"))
    )
    (net (code "89") (name "Net-(IC22A-I1)") (class "Default")
      (node (ref "IC22") (pin "2") (pinfunction "I1_2") (pintype "input"))
      (node (ref "IC23") (pin "4") (pinfunction "O_4") (pintype "output"))
    )
    (net (code "90") (name "Net-(LED1-PadA)") (class "Default")
      (node (ref "LED1") (pin "A") (pinfunction "A_A") (pintype "passive"))
      (node (ref "R7") (pin "1") (pinfunction "1_1") (pintype "passive"))
    )
    (net (code "91") (name "Net-(PAD1-P)") (class "Default")
      (node (ref "PAD1") (pin "1") (pinfunction "P_1") (pintype "passive"))
      (node (ref "R3") (pin "1") (pinfunction "1_1") (pintype "passive"))
    )
    (net (code "92") (name "Net-(U$5-4NS)") (class "Default")
      (node (ref "JP1") (pin "3") (pinfunction "3_3") (pintype "passive"))
      (node (ref "U$5") (pin "7") (pinfunction "4NS_7") (pintype "bidirectional"))
    )
    (net (code "93") (name "Net-(U$5-8NS)") (class "Default")
      (node (ref "JP1") (pin "5") (pinfunction "5_5") (pintype "passive"))
      (node (ref "U$5") (pin "2") (pinfunction "8NS_2") (pintype "bidirectional"))
    )
    (net (code "94") (name "Net-(U$5-12NS)") (class "Default")
      (node (ref "JP1") (pin "7") (pinfunction "7_7") (pintype "passive"))
      (node (ref "U$5") (pin "6") (pinfunction "12NS_6") (pintype "bidirectional"))
    )
    (net (code "95") (name "PICO") (class "Default")
      (node (ref "IC1") (pin "14") (pinfunction "SER_14") (pintype "input"))
      (node (ref "J1") (pin "A2") (pinfunction "A2_A2") (pintype "passive"))
    )
    (net (code "96") (name "PROG") (class "Default")
      (node (ref "IC18") (pin "16") (pinfunction "3Y3_16") (pintype "tri_state"))
      (node (ref "IC23") (pin "2") (pinfunction "I_2") (pintype "input"))
      (node (ref "J1") (pin "C27") (pinfunction "C27_C27") (pintype "passive"))
    )
    (net (code "97") (name "RCLK") (class "Default")
      (node (ref "IC1") (pin "12") (pinfunction "RCLK_12") (pintype "input"))
      (node (ref "IC14") (pin "4") (pinfunction "O_4") (pintype "output"))
      (node (ref "IC2") (pin "12") (pinfunction "RCLK_12") (pintype "input"))
      (node (ref "IC3") (pin "12") (pinfunction "RCLK_12") (pintype "input"))
      (node (ref "IC4") (pin "12") (pinfunction "RCLK_12") (pintype "input"))
    )
    (net (code "98") (name "RES") (class "Default")
      (node (ref "IC18") (pin "17") (pinfunction "3Y4_17") (pintype "tri_state"))
      (node (ref "J1") (pin "C28") (pinfunction "C28_C28") (pintype "passive"))
    )
    (net (code "99") (name "SCLK") (class "Default")
      (node (ref "IC1") (pin "11") (pinfunction "SRCLK_11") (pintype "input"))
      (node (ref "IC19") (pin "4") (pinfunction "O_4") (pintype "output"))
      (node (ref "IC2") (pin "11") (pinfunction "SRCLK_11") (pintype "input"))
      (node (ref "IC20") (pin "2") (pinfunction "I_2") (pintype "input"))
      (node (ref "IC3") (pin "11") (pinfunction "SRCLK_11") (pintype "input"))
      (node (ref "IC4") (pin "11") (pinfunction "SRCLK_11") (pintype "input"))
      (node (ref "JP1") (pin "1") (pinfunction "1_1") (pintype "passive"))
      (node (ref "U$5") (pin "1") (pinfunction "CLK_IN_1") (pintype "bidirectional"))
    )
    (net (code "100") (name "SPI_RESET") (class "Default")
      (node (ref "IC10") (pin "1") (pinfunction "I0_1") (pintype "input"))
      (node (ref "J1") (pin "A5") (pinfunction "A5_A5") (pintype "passive"))
      (node (ref "R2") (pin "1") (pinfunction "1_1") (pintype "passive"))
    )
    (net (code "101") (name "SRCLR") (class "Default")
      (node (ref "IC1") (pin "10") (pinfunction "~{SRCLR}_10") (pintype "input"))
      (node (ref "IC2") (pin "10") (pinfunction "~{SRCLR}_10") (pintype "input"))
      (node (ref "IC3") (pin "10") (pinfunction "~{SRCLR}_10") (pintype "input"))
      (node (ref "IC4") (pin "10") (pinfunction "~{SRCLR}_10") (pintype "input"))
      (node (ref "IC8") (pin "4") (pinfunction "O_4") (pintype "output"))
    )
    (net (code "102") (name "VCC") (class "Default")
      (node (ref "C10") (pin "1") (pinfunction "1_1") (pintype "passive"))
      (node (ref "C11") (pin "1") (pinfunction "1_1") (pintype "passive"))
      (node (ref "C12") (pin "1") (pinfunction "1_1") (pintype "passive"))
      (node (ref "C14") (pin "1") (pinfunction "1_1") (pintype "passive"))
      (node (ref "C15") (pin "1") (pinfunction "1_1") (pintype "passive"))
      (node (ref "C16") (pin "1") (pinfunction "1_1") (pintype "passive"))
      (node (ref "C17") (pin "1") (pinfunction "1_1") (pintype "passive"))
      (node (ref "C18") (pin "1") (pinfunction "1_1") (pintype "passive"))
      (node (ref "C19") (pin "1") (pinfunction "1_1") (pintype "passive"))
      (node (ref "C20") (pin "1") (pinfunction "1_1") (pintype "passive"))
      (node (ref "C21") (pin "1") (pinfunction "1_1") (pintype "passive"))
      (node (ref "C22") (pin "1") (pinfunction "1_1") (pintype "passive"))
      (node (ref "C23") (pin "1") (pinfunction "1_1") (pintype "passive"))
      (node (ref "C24") (pin "1") (pinfunction "1_1") (pintype "passive"))
      (node (ref "C4") (pin "1") (pinfunction "1_1") (pintype "passive"))
      (node (ref "C5") (pin "1") (pinfunction "1_1") (pintype "passive"))
      (node (ref "C6") (pin "1") (pinfunction "1_1") (pintype "passive"))
      (node (ref "C7") (pin "1") (pinfunction "1_1") (pintype "passive"))
      (node (ref "C8") (pin "1") (pinfunction "1_1") (pintype "passive"))
      (node (ref "C9") (pin "1") (pinfunction "1_1") (pintype "passive"))
      (node (ref "IC1") (pin "16") (pinfunction "VCC_16") (pintype "bidirectional"))
      (node (ref "IC2") (pin "16") (pinfunction "VCC_16") (pintype "bidirectional"))
      (node (ref "IC3") (pin "16") (pinfunction "VCC_16") (pintype "bidirectional"))
      (node (ref "IC4") (pin "16") (pinfunction "VCC_16") (pintype "bidirectional"))
      (node (ref "PAD2") (pin "1") (pinfunction "P_1") (pintype "passive"))
      (node (ref "R1") (pin "2") (pinfunction "2_2") (pintype "passive"))
      (node (ref "R4") (pin "2") (pinfunction "2_2") (pintype "passive"))
      (node (ref "U$5") (pin "8") (pinfunction "3.3V_8") (pintype "bidirectional"))
      (node (ref "U$9") (pin "2") (pinfunction "VCC_2") (pintype "power_in"))
      (node (ref "U$9") (pin "4") (pinfunction "VCC_4") (pintype "power_in"))
    )
    (net (code "103") (name "WE") (class "Default")
      (node (ref "IC18") (pin "20") (pinfunction "4Y2_20") (pintype "tri_state"))
      (node (ref "J1") (pin "C30") (pinfunction "C30_C30") (pintype "passive"))
    )
    (net (code "104") (name "unconnected-(IC4-Q7S-Pad9)") (class "Default")
      (node (ref "IC4") (pin "9") (pinfunction "Q7S_9") (pintype "output"))
    )
    (net (code "105") (name "unconnected-(IC7A-QA-Pad3)") (class "Default")
      (node (ref "IC7") (pin "3") (pinfunction "QA_3") (pintype "output"))
    )
    (net (code "106") (name "unconnected-(IC7A-QB-Pad4)") (class "Default")
      (node (ref "IC7") (pin "4") (pinfunction "QB_4") (pintype "output"))
    )
    (net (code "107") (name "unconnected-(IC7A-QC-Pad5)") (class "Default")
      (node (ref "IC7") (pin "5") (pinfunction "QC_5") (pintype "output"))
    )
    (net (code "108") (name "unconnected-(IC7B-QB-Pad10)") (class "Default")
      (node (ref "IC7") (pin "10") (pinfunction "QB_10") (pintype "output"))
    )
    (net (code "109") (name "unconnected-(IC7B-QC-Pad9)") (class "Default")
      (node (ref "IC7") (pin "9") (pinfunction "QC_9") (pintype "output"))
    )
    (net (code "110") (name "unconnected-(IC7B-QD-Pad8)") (class "Default")
      (node (ref "IC7") (pin "8") (pinfunction "QD_8") (pintype "output"))
    )
    (net (code "111") (name "unconnected-(J1-PadA3)") (class "Default")
      (node (ref "J1") (pin "A3") (pinfunction "A3_A3") (pintype "passive"))
    )
    (net (code "112") (name "unconnected-(J1-PadA4)") (class "Default")
      (node (ref "J1") (pin "A4") (pinfunction "A4_A4") (pintype "passive"))
    )
    (net (code "113") (name "unconnected-(J1-PadA6)") (class "Default")
      (node (ref "J1") (pin "A6") (pinfunction "A6_A6") (pintype "passive"))
    )
    (net (code "114") (name "unconnected-(J1-PadA7)") (class "Default")
      (node (ref "J1") (pin "A7") (pinfunction "A7_A7") (pintype "passive"))
    )
    (net (code "115") (name "unconnected-(J1-PadA8)") (class "Default")
      (node (ref "J1") (pin "A8") (pinfunction "A8_A8") (pintype "passive"))
    )
    (net (code "116") (name "unconnected-(J1-PadA25)") (class "Default")
      (node (ref "J1") (pin "A25") (pinfunction "A25_A25") (pintype "passive"))
    )
    (net (code "117") (name "unconnected-(U$5-16NS-Pad3)") (class "Default")
      (node (ref "U$5") (pin "3") (pinfunction "16NS_3") (pintype "bidirectional"))
    )
    (net (code "118") (name "unconnected-(U$5-20NS-Pad5)") (class "Default")
      (node (ref "U$5") (pin "5") (pinfunction "20NS_5") (pintype "bidirectional"))
    )
  )
)
